# MCU.net
KiCad netlist of a schematic drawn in Altium Designer
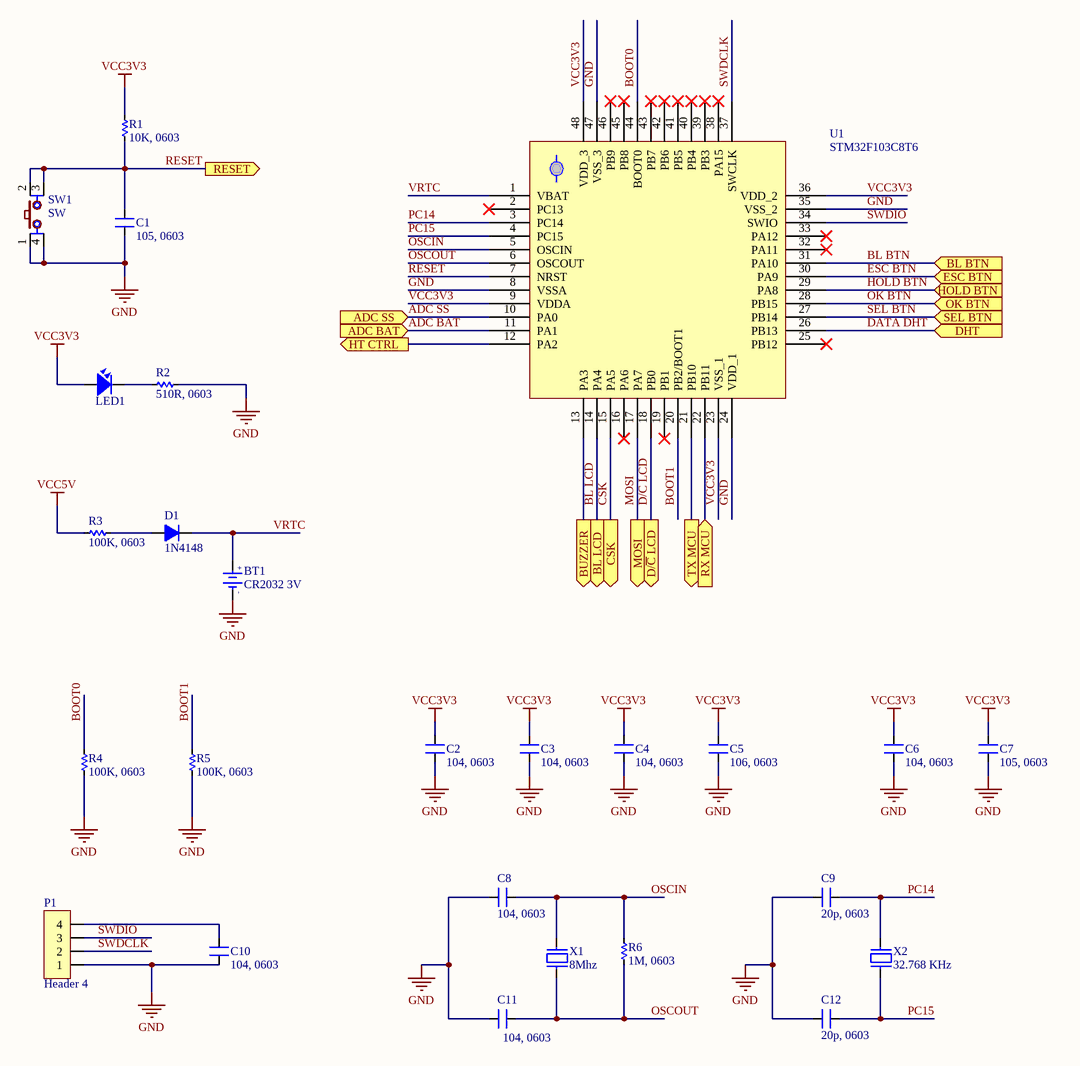
[diagram p0: MCU.SchDoc]

(export (version "E")
  (design (tool "Eeschema 10.0.6"))
  (components
    (comp (ref "BT1")
      (value "CR2032 3V")
      (footprint "PIN3V")
      (description "CR2032 3VDC rechargeable")
      (libsource (lib "KhanhBK_SCH_Library_1") (part "PIN 3V"))
    )
    (comp (ref "C1")
      (value "105, 0603")
      (footprint "SM-0603")
      (description "Cap SMD")
      (libsource (lib "KhanhBK_Library_4") (part "CM"))
    )
    (comp (ref "C2")
      (value "104, 0603")
      (footprint "SM-0603")
      (description "Cap SMD")
      (libsource (lib "KhanhBK_Library_4") (part "CM"))
    )
    (comp (ref "C3")
      (value "104, 0603")
      (footprint "SM-0603")
      (description "Cap SMD")
      (libsource (lib "KhanhBK_Library_4") (part "CM"))
    )
    (comp (ref "C4")
      (value "104, 0603")
      (footprint "SM-0603")
      (description "Cap SMD")
      (libsource (lib "KhanhBK_Library_4") (part "CM"))
    )
    (comp (ref "C5")
      (value "106, 0603")
      (footprint "SM-0603")
      (description "Cap SMD")
      (libsource (lib "KhanhBK_Library_4") (part "CM"))
    )
    (comp (ref "C6")
      (value "104, 0603")
      (footprint "SM-0603")
      (description "Cap SMD")
      (libsource (lib "KhanhBK_Library_4") (part "CM"))
    )
    (comp (ref "C7")
      (value "105, 0603")
      (footprint "SM-0603")
      (description "Cap SMD")
      (libsource (lib "KhanhBK_Library_4") (part "CM"))
    )
    (comp (ref "C8")
      (value "104, 0603")
      (footprint "SM-0603")
      (description "Cap SMD")
      (libsource (lib "KhanhBK_Library_4") (part "CM"))
    )
    (comp (ref "C9")
      (value "20p, 0603")
      (footprint "SM-0603")
      (description "Cap SMD")
      (libsource (lib "KhanhBK_Library_4") (part "CM"))
    )
    (comp (ref "C10")
      (value "104, 0603")
      (footprint "SM-0603")
      (description "Cap SMD")
      (libsource (lib "KhanhBK_Library_4") (part "CM"))
    )
    (comp (ref "C11")
      (value "104, 0603")
      (footprint "SM-0603")
      (description "Cap SMD")
      (libsource (lib "KhanhBK_Library_4") (part "CM"))
    )
    (comp (ref "C12")
      (value "20p, 0603")
      (footprint "SM-0603")
      (description "Cap SMD")
      (libsource (lib "KhanhBK_Library_4") (part "CM"))
    )
    (comp (ref "D1")
      (value "1N4148")
      (footprint "D0.5A")
      (description "D0.5A")
      (libsource (lib "KhanhBK_SCH_Library_2") (part "D0.5A"))
    )
    (comp (ref "LED1")
      (value "LED")
      (footprint "LED-0805-Blue")
      (libsource (lib "KhanhBK_SCH_Library_1") (part "LED SMD"))
    )
    (comp (ref "P1")
      (value "Header 4")
      (footprint "HDR/Header/4")
      (description "Header, 4-Pin")
      (libsource (lib "connectors") (part "Header 4"))
    )
    (comp (ref "R1")
      (value "10K, 0603")
      (footprint "RES-SMD-0603")
      (description "Resistor")
      (fields
        (field (name "MANUFACTURER") "Generic Components")
        (field (name "PUBLISHER") "Altium Hobart Technology Centre")
      )
      (libsource (lib "KhanhBK_SCH_Library_1") (part "Res-SMD"))
    )
    (comp (ref "R2")
      (value "510R, 0603")
      (footprint "RES-SMD-0603")
      (description "Resistor")
      (fields
        (field (name "MANUFACTURER") "Generic Components")
        (field (name "PUBLISHER") "Altium Hobart Technology Centre")
      )
      (libsource (lib "KhanhBK_SCH_Library_1") (part "Res-SMD"))
    )
    (comp (ref "R3")
      (value "100K, 0603")
      (footprint "RES-SMD-0603")
      (description "Resistor")
      (fields
        (field (name "MANUFACTURER") "Generic Components")
        (field (name "PUBLISHER") "Altium Hobart Technology Centre")
      )
      (libsource (lib "KhanhBK_SCH_Library_1") (part "Res-SMD"))
    )
    (comp (ref "R4")
      (value "100K, 0603")
      (footprint "RES-SMD-0603")
      (description "Resistor")
      (fields
        (field (name "MANUFACTURER") "Generic Components")
        (field (name "PUBLISHER") "Altium Hobart Technology Centre")
      )
      (libsource (lib "KhanhBK_SCH_Library_1") (part "Res-SMD"))
    )
    (comp (ref "R5")
      (value "100K, 0603")
      (footprint "RES-SMD-0603")
      (description "Resistor")
      (fields
        (field (name "MANUFACTURER") "Generic Components")
        (field (name "PUBLISHER") "Altium Hobart Technology Centre")
      )
      (libsource (lib "KhanhBK_SCH_Library_1") (part "Res-SMD"))
    )
    (comp (ref "R6")
      (value "1M, 0603")
      (footprint "RES-SMD-0603")
      (description "Resistor")
      (fields
        (field (name "MANUFACTURER") "Generic Components")
        (field (name "PUBLISHER") "Altium Hobart Technology Centre")
      )
      (libsource (lib "KhanhBK_SCH_Library_1") (part "Res-SMD"))
    )
    (comp (ref "SW1")
      (value "SW")
      (footprint "SW2-SMD")
      (description "Switch button 4 pin")
      (libsource (lib "KhanhBK_SCH_Library_1") (part "SW4"))
    )
    (comp (ref "U1")
      (value "STM32F103C8T6")
      (footprint "QFP50P900X900X160-48N")
      (libsource (lib "Project2_Library") (part "STM32F103C8T6"))
    )
    (comp (ref "X1")
      (value "8Mhz")
      (footprint "XT2")
      (description "Crystal For all Crystal 2pin.")
      (libsource (lib "KhanhBK_SCH_Library_2") (part "XT2"))
    )
    (comp (ref "X2")
      (value "32.768 KHz")
      (footprint "XT2-SMD")
      (description "Crystal, 32.768 KHz, -40 to 85 degC, 3.2 x 1.5 x 0.9 mm SMD")
      (libsource (lib "KhanhBK_SCH_Library_1") (part "XT2"))
    )
  )
  (nets
    (net (code "1") (name "/ADC BAT") (class "Default")
      (node (ref "U1") (pin "11") (pinfunction "PA1_11") (pintype "passive"))
    )
    (net (code "2") (name "/ADC SS") (class "Default")
      (node (ref "U1") (pin "10") (pinfunction "PA0_10") (pintype "passive"))
    )
    (net (code "3") (name "/BL BTN") (class "Default")
      (node (ref "U1") (pin "31") (pinfunction "PA10_31") (pintype "passive"))
    )
    (net (code "4") (name "/BL LCD") (class "Default")
      (node (ref "U1") (pin "14") (pinfunction "PA4_14") (pintype "passive"))
    )
    (net (code "5") (name "/BOOT0") (class "Default")
      (node (ref "R4") (pin "1") (pinfunction "1_1") (pintype "passive"))
      (node (ref "U1") (pin "44") (pinfunction "BOOT0_44") (pintype "passive"))
    )
    (net (code "6") (name "/BOOT1") (class "Default")
      (node (ref "R5") (pin "1") (pinfunction "1_1") (pintype "passive"))
      (node (ref "U1") (pin "20") (pinfunction "PB2/BOOT1_20") (pintype "passive"))
    )
    (net (code "7") (name "/BUZZER") (class "Default")
      (node (ref "U1") (pin "13") (pinfunction "PA3_13") (pintype "passive"))
    )
    (net (code "8") (name "/CSK") (class "Default")
      (node (ref "U1") (pin "15") (pinfunction "PA5_15") (pintype "passive"))
    )
    (net (code "9") (name "/DATA DHT") (class "Default")
      (node (ref "U1") (pin "26") (pinfunction "PB13_26") (pintype "passive"))
    )
    (net (code "10") (name "/D{slash}~{C} LCD") (class "Default")
      (node (ref "U1") (pin "18") (pinfunction "PB0_18") (pintype "passive"))
    )
    (net (code "11") (name "/ESC BTN") (class "Default")
      (node (ref "U1") (pin "30") (pinfunction "PA9_30") (pintype "passive"))
    )
    (net (code "12") (name "/HOLD BTN") (class "Default")
      (node (ref "U1") (pin "29") (pinfunction "PA8_29") (pintype "passive"))
    )
    (net (code "13") (name "/HT CTRL") (class "Default")
      (node (ref "U1") (pin "12") (pinfunction "PA2_12") (pintype "passive"))
    )
    (net (code "14") (name "/MOSI") (class "Default")
      (node (ref "U1") (pin "17") (pinfunction "PA7_17") (pintype "passive"))
    )
    (net (code "15") (name "/OK BTN") (class "Default")
      (node (ref "U1") (pin "28") (pinfunction "PB15_28") (pintype "passive"))
    )
    (net (code "16") (name "/OSCIN") (class "Default")
      (node (ref "C8") (pin "2") (pinfunction "2_2") (pintype "passive"))
      (node (ref "R6") (pin "1") (pinfunction "1_1") (pintype "passive"))
      (node (ref "U1") (pin "5") (pinfunction "OSCIN_5") (pintype "passive"))
      (node (ref "X1") (pin "2") (pinfunction "2_2") (pintype "passive"))
    )
    (net (code "17") (name "/OSCOUT") (class "Default")
      (node (ref "C11") (pin "1") (pinfunction "1_1") (pintype "passive"))
      (node (ref "R6") (pin "2") (pinfunction "2_2") (pintype "passive"))
      (node (ref "U1") (pin "6") (pinfunction "OSCOUT_6") (pintype "passive"))
      (node (ref "X1") (pin "1") (pinfunction "1_1") (pintype "passive"))
    )
    (net (code "18") (name "/PC14") (class "Default")
      (node (ref "C9") (pin "1") (pinfunction "1_1") (pintype "passive"))
      (node (ref "U1") (pin "3") (pinfunction "PC14_3") (pintype "passive"))
      (node (ref "X2") (pin "2") (pinfunction "2_2") (pintype "passive"))
    )
    (net (code "19") (name "/PC15") (class "Default")
      (node (ref "C12") (pin "1") (pinfunction "1_1") (pintype "passive"))
      (node (ref "U1") (pin "4") (pinfunction "PC15_4") (pintype "passive"))
      (node (ref "X2") (pin "1") (pinfunction "1_1") (pintype "passive"))
    )
    (net (code "20") (name "/RESET") (class "Default")
      (node (ref "C1") (pin "2") (pinfunction "2_2") (pintype "passive"))
      (node (ref "R1") (pin "1") (pinfunction "1_1") (pintype "passive"))
      (node (ref "SW1") (pin "2") (pinfunction "2_2") (pintype "passive"))
      (node (ref "SW1") (pin "3") (pinfunction "3_3") (pintype "passive"))
      (node (ref "U1") (pin "7") (pinfunction "NRST_7") (pintype "passive"))
    )
    (net (code "21") (name "/RX MCU") (class "Default")
      (node (ref "U1") (pin "22") (pinfunction "PB11_22") (pintype "passive"))
    )
    (net (code "22") (name "/SEL BTN") (class "Default")
      (node (ref "U1") (pin "27") (pinfunction "PB14_27") (pintype "passive"))
    )
    (net (code "23") (name "/SWDCLK") (class "Default")
      (node (ref "P1") (pin "2") (pinfunction "2_2") (pintype "passive"))
      (node (ref "U1") (pin "37") (pinfunction "SWCLK_37") (pintype "passive"))
    )
    (net (code "24") (name "/SWDIO") (class "Default")
      (node (ref "P1") (pin "3") (pinfunction "3_3") (pintype "passive"))
      (node (ref "U1") (pin "34") (pinfunction "SWIO_34") (pintype "passive"))
    )
    (net (code "25") (name "/TX MCU") (class "Default")
      (node (ref "U1") (pin "21") (pinfunction "PB10_21") (pintype "passive"))
    )
    (net (code "26") (name "/VRTC") (class "Default")
      (node (ref "BT1") (pin "1") (pinfunction "+3V_1") (pintype "passive"))
      (node (ref "D1") (pin "2") (pinfunction "K_2") (pintype "passive"))
      (node (ref "U1") (pin "1") (pinfunction "VBAT_1") (pintype "passive"))
    )
    (net (code "27") (name "GND") (class "Default")
      (node (ref "BT1") (pin "2") (pinfunction "GND_2") (pintype "passive"))
      (node (ref "C1") (pin "1") (pinfunction "1_1") (pintype "passive"))
      (node (ref "C10") (pin "1") (pinfunction "1_1") (pintype "passive"))
      (node (ref "C11") (pin "2") (pinfunction "2_2") (pintype "passive"))
      (node (ref "C12") (pin "2") (pinfunction "2_2") (pintype "passive"))
      (node (ref "C2") (pin "1") (pinfunction "1_1") (pintype "passive"))
      (node (ref "C3") (pin "1") (pinfunction "1_1") (pintype "passive"))
      (node (ref "C4") (pin "1") (pinfunction "1_1") (pintype "passive"))
      (node (ref "C5") (pin "1") (pinfunction "1_1") (pintype "passive"))
      (node (ref "C6") (pin "1") (pinfunction "1_1") (pintype "passive"))
      (node (ref "C7") (pin "1") (pinfunction "1_1") (pintype "passive"))
      (node (ref "C8") (pin "1") (pinfunction "1_1") (pintype "passive"))
      (node (ref "C9") (pin "2") (pinfunction "2_2") (pintype "passive"))
      (node (ref "P1") (pin "1") (pinfunction "1_1") (pintype "passive"))
      (node (ref "R2") (pin "2") (pinfunction "2_2") (pintype "passive"))
      (node (ref "R4") (pin "2") (pinfunction "2_2") (pintype "passive"))
      (node (ref "R5") (pin "2") (pinfunction "2_2") (pintype "passive"))
      (node (ref "SW1") (pin "1") (pintype "passive"))
      (node (ref "SW1") (pin "4") (pinfunction "4_4") (pintype "passive"))
      (node (ref "U1") (pin "24") (pinfunction "VDD_1_24") (pintype "passive"))
      (node (ref "U1") (pin "35") (pinfunction "VSS_2_35") (pintype "passive"))
      (node (ref "U1") (pin "47") (pinfunction "VSS_3_47") (pintype "passive"))
      (node (ref "U1") (pin "8") (pinfunction "VSSA_8") (pintype "passive"))
    )
    (net (code "28") (name "Net-(C10-Pad2)") (class "Default")
      (node (ref "C10") (pin "2") (pinfunction "2_2") (pintype "passive"))
      (node (ref "P1") (pin "4") (pinfunction "4_4") (pintype "passive"))
    )
    (net (code "29") (name "Net-(D1-A)") (class "Default")
      (node (ref "D1") (pin "1") (pinfunction "A_1") (pintype "passive"))
      (node (ref "R3") (pin "2") (pinfunction "2_2") (pintype "passive"))
    )
    (net (code "30") (name "Net-(LED1-Pad2)") (class "Default")
      (node (ref "LED1") (pin "2") (pinfunction "2_2") (pintype "passive"))
      (node (ref "R2") (pin "1") (pinfunction "1_1") (pintype "passive"))
    )
    (net (code "31") (name "VCC3V3") (class "Default")
      (node (ref "C2") (pin "2") (pinfunction "2_2") (pintype "passive"))
      (node (ref "C3") (pin "2") (pinfunction "2_2") (pintype "passive"))
      (node (ref "C4") (pin "2") (pinfunction "2_2") (pintype "passive"))
      (node (ref "C5") (pin "2") (pinfunction "2_2") (pintype "passive"))
      (node (ref "C6") (pin "2") (pinfunction "2_2") (pintype "passive"))
      (node (ref "C7") (pin "2") (pinfunction "2_2") (pintype "passive"))
      (node (ref "LED1") (pin "1") (pinfunction "1_1") (pintype "passive"))
      (node (ref "R1") (pin "2") (pinfunction "2_2") (pintype "passive"))
      (node (ref "U1") (pin "23") (pinfunction "VSS_1_23") (pintype "passive"))
      (node (ref "U1") (pin "36") (pinfunction "VDD_2_36") (pintype "passive"))
      (node (ref "U1") (pin "48") (pinfunction "VDD_3_48") (pintype "passive"))
      (node (ref "U1") (pin "9") (pinfunction "VDDA_9") (pintype "passive"))
    )
    (net (code "32") (name "VCC5V") (class "Default")
      (node (ref "R3") (pin "1") (pinfunction "1_1") (pintype "passive"))
    )
    (net (code "33") (name "unconnected-(U1-PA6-Pad16)") (class "Default")
      (node (ref "U1") (pin "16") (pinfunction "PA6_16") (pintype "passive+no_connect"))
    )
    (net (code "34") (name "unconnected-(U1-PA11-Pad32)") (class "Default")
      (node (ref "U1") (pin "32") (pinfunction "PA11_32") (pintype "passive+no_connect"))
    )
    (net (code "35") (name "unconnected-(U1-PA12-Pad33)") (class "Default")
      (node (ref "U1") (pin "33") (pinfunction "PA12_33") (pintype "passive+no_connect"))
    )
    (net (code "36") (name "unconnected-(U1-PA15-Pad38)") (class "Default")
      (node (ref "U1") (pin "38") (pinfunction "PA15_38") (pintype "passive+no_connect"))
    )
    (net (code "37") (name "unconnected-(U1-PB1-Pad19)") (class "Default")
      (node (ref "U1") (pin "19") (pinfunction "PB1_19") (pintype "passive+no_connect"))
    )
    (net (code "38") (name "unconnected-(U1-PB3-Pad39)") (class "Default")
      (node (ref "U1") (pin "39") (pinfunction "PB3_39") (pintype "passive+no_connect"))
    )
    (net (code "39") (name "unconnected-(U1-PB4-Pad40)") (class "Default")
      (node (ref "U1") (pin "40") (pinfunction "PB4_40") (pintype "passive+no_connect"))
    )
    (net (code "40") (name "unconnected-(U1-PB5-Pad41)") (class "Default")
      (node (ref "U1") (pin "41") (pinfunction "PB5_41") (pintype "passive+no_connect"))
    )
    (net (code "41") (name "unconnected-(U1-PB6-Pad42)") (class "Default")
      (node (ref "U1") (pin "42") (pinfunction "PB6_42") (pintype "passive+no_connect"))
    )
    (net (code "42") (name "unconnected-(U1-PB7-Pad43)") (class "Default")
      (node (ref "U1") (pin "43") (pinfunction "PB7_43") (pintype "passive+no_connect"))
    )
    (net (code "43") (name "unconnected-(U1-PB8-Pad45)") (class "Default")
      (node (ref "U1") (pin "45") (pinfunction "PB8_45") (pintype "passive+no_connect"))
    )
    (net (code "44") (name "unconnected-(U1-PB9-Pad46)") (class "Default")
      (node (ref "U1") (pin "46") (pinfunction "PB9_46") (pintype "passive+no_connect"))
    )
    (net (code "45") (name "unconnected-(U1-PB12-Pad25)") (class "Default")
      (node (ref "U1") (pin "25") (pinfunction "PB12_25") (pintype "passive+no_connect"))
    )
    (net (code "46") (name "unconnected-(U1-PC13-Pad2)") (class "Default")
      (node (ref "U1") (pin "2") (pinfunction "PC13_2") (pintype "passive+no_connect"))
    )
  )
)
